# roomba_main_pcb_v1.net
KiCad netlist of a schematic drawn in EAGLE
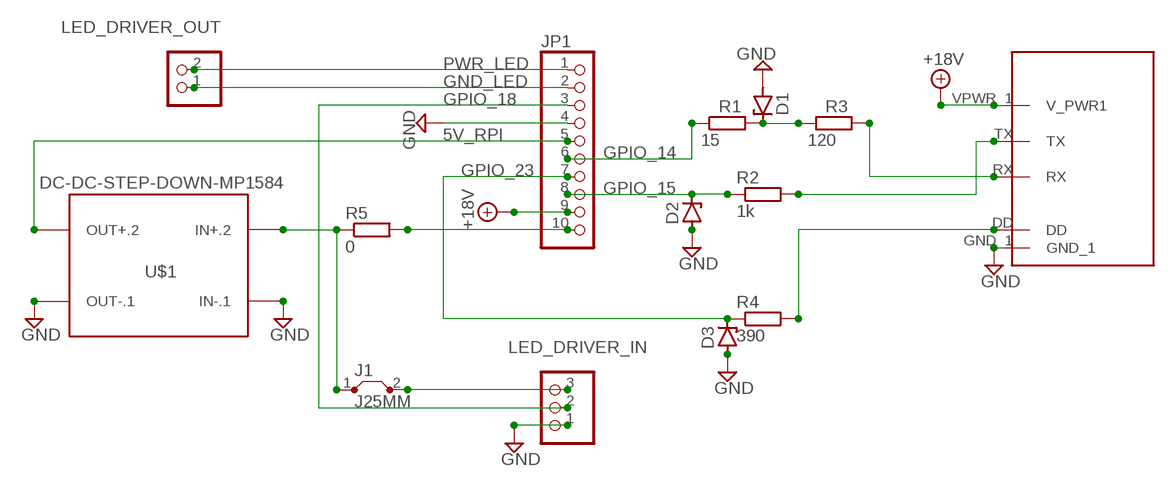
[diagram p0: schematic, sheet 1]

(export (version "E")
  (design (tool "Eeschema 10.0.6"))
  (components
    (comp (ref "D1")
      (value "ZENER-DIODESOD80C")
      (footprint "eagle-import:SOD80C")
      (libsource (lib "eagle-import") (part "ZENER-DIODESOD80C"))
    )
    (comp (ref "D2")
      (value "ZENER-DIODESOD80C")
      (footprint "eagle-import:SOD80C")
      (libsource (lib "eagle-import") (part "ZENER-DIODESOD80C"))
    )
    (comp (ref "D3")
      (value "ZENER-DIODESOD80C")
      (footprint "eagle-import:SOD80C")
      (libsource (lib "eagle-import") (part "ZENER-DIODESOD80C"))
    )
    (comp (ref "J1")
      (value "J25MM")
      (footprint "eagle-import:25")
      (libsource (lib "eagle-import") (part "J25MM"))
    )
    (comp (ref "JP1")
      (value "PINHD-1X10/90")
      (footprint "eagle-import:1X10_90")
      (libsource (lib "eagle-import") (part "PINHD-1X10/90"))
    )
    (comp (ref "LED_DRIVER_IN")
      (value "PINHD-1X3")
      (footprint "eagle-import:1X03")
      (libsource (lib "eagle-import") (part "PINHD-1X3"))
    )
    (comp (ref "LED_DRIVER_OUT")
      (value "PINHD-1X2")
      (footprint "eagle-import:1X02")
      (libsource (lib "eagle-import") (part "PINHD-1X2"))
    )
    (comp (ref "R1")
      (value "15")
      (footprint "eagle-import:M1206")
      (libsource (lib "eagle-import") (part "R-EU_M1206"))
    )
    (comp (ref "R2")
      (value "1k")
      (footprint "eagle-import:M1206")
      (libsource (lib "eagle-import") (part "R-EU_M1206"))
    )
    (comp (ref "R3")
      (value "120")
      (footprint "eagle-import:M1206")
      (libsource (lib "eagle-import") (part "R-EU_M1206"))
    )
    (comp (ref "R4")
      (value "390")
      (footprint "eagle-import:M1206")
      (libsource (lib "eagle-import") (part "R-EU_M1206"))
    )
    (comp (ref "R5")
      (value "0")
      (footprint "eagle-import:M1206")
      (libsource (lib "eagle-import") (part "R-EU_M1206"))
    )
    (comp (ref "ROOMBA_PORT")
      (value "7_PIN")
      (footprint "eagle-import:PIN-7")
      (libsource (lib "eagle-import") (part "7_PIN"))
    )
    (comp (ref "U$1")
      (value "DC-DC-STEP-DOWN-MP1584")
      (footprint "eagle-import:DC-DC-STEP-DOWN-MP1584")
      (libsource (lib "eagle-import") (part "DC-DC-STEP-DOWN-MP1584"))
    )
  )
  (nets
    (net (code "1") (name "+18V") (class "Default")
      (node (ref "JP1") (pin "9") (pinfunction "9_9") (pintype "passive"))
      (node (ref "ROOMBA_PORT") (pin "VPWR_1") (pinfunction "V_PWR1_VPWR_1") (pintype "bidirectional"))
    )
    (net (code "2") (name "/5V_RPI") (class "Default")
      (node (ref "JP1") (pin "5") (pinfunction "5_5") (pintype "passive"))
      (node (ref "U$1") (pin "OUT+.2") (pinfunction "OUT+.2_OUT+.2") (pintype "bidirectional"))
    )
    (net (code "3") (name "/GND_LED") (class "Default")
      (node (ref "JP1") (pin "2") (pinfunction "2_2") (pintype "passive"))
      (node (ref "LED_DRIVER_OUT") (pin "1") (pinfunction "1_1") (pintype "passive"))
    )
    (net (code "4") (name "/GPIO_14") (class "Default")
      (node (ref "JP1") (pin "6") (pinfunction "6_6") (pintype "passive"))
      (node (ref "R1") (pin "1") (pinfunction "1_1") (pintype "passive"))
    )
    (net (code "5") (name "/GPIO_15") (class "Default")
      (node (ref "D2") (pin "C") (pinfunction "C_C") (pintype "passive"))
      (node (ref "JP1") (pin "8") (pinfunction "8_8") (pintype "passive"))
      (node (ref "R2") (pin "1") (pinfunction "1_1") (pintype "passive"))
    )
    (net (code "6") (name "/GPIO_18") (class "Default")
      (node (ref "JP1") (pin "3") (pinfunction "3_3") (pintype "passive"))
      (node (ref "LED_DRIVER_IN") (pin "2") (pinfunction "2_2") (pintype "passive"))
    )
    (net (code "7") (name "/GPIO_23") (class "Default")
      (node (ref "D3") (pin "C") (pinfunction "C_C") (pintype "passive"))
      (node (ref "JP1") (pin "7") (pinfunction "7_7") (pintype "passive"))
      (node (ref "R4") (pin "1") (pinfunction "1_1") (pintype "passive"))
    )
    (net (code "8") (name "/PWR_LED") (class "Default")
      (node (ref "JP1") (pin "1") (pinfunction "1_1") (pintype "passive"))
      (node (ref "LED_DRIVER_OUT") (pin "2") (pinfunction "2_2") (pintype "passive"))
    )
    (net (code "9") (name "GND") (class "Default")
      (node (ref "D1") (pin "A") (pinfunction "A_A") (pintype "passive"))
      (node (ref "D2") (pin "A") (pinfunction "A_A") (pintype "passive"))
      (node (ref "D3") (pin "A") (pinfunction "A_A") (pintype "passive"))
      (node (ref "JP1") (pin "4") (pinfunction "4_4") (pintype "passive"))
      (node (ref "LED_DRIVER_IN") (pin "1") (pinfunction "1_1") (pintype "passive"))
      (node (ref "ROOMBA_PORT") (pin "GND_1") (pinfunction "GND_1_GND_1") (pintype "bidirectional"))
      (node (ref "U$1") (pin "IN-.1") (pinfunction "IN-.1_IN-.1") (pintype "bidirectional"))
      (node (ref "U$1") (pin "OUT-.1") (pinfunction "OUT-.1_OUT-.1") (pintype "bidirectional"))
    )
    (net (code "10") (name "Net-(D1-PadC)") (class "Default")
      (node (ref "D1") (pin "C") (pinfunction "C_C") (pintype "passive"))
      (node (ref "R1") (pin "2") (pinfunction "2_2") (pintype "passive"))
      (node (ref "R3") (pin "1") (pinfunction "1_1") (pintype "passive"))
    )
    (net (code "11") (name "Net-(J1-Pad1)") (class "Default")
      (node (ref "J1") (pin "1") (pinfunction "1_1") (pintype "passive"))
      (node (ref "R5") (pin "1") (pinfunction "1_1") (pintype "passive"))
      (node (ref "U$1") (pin "IN+.2") (pinfunction "IN+.2_IN+.2") (pintype "bidirectional"))
    )
    (net (code "12") (name "Net-(J1-Pad2)") (class "Default")
      (node (ref "J1") (pin "2") (pinfunction "2_2") (pintype "passive"))
      (node (ref "LED_DRIVER_IN") (pin "3") (pinfunction "3_3") (pintype "passive"))
    )
    (net (code "13") (name "Net-(JP1-Pad10)") (class "Default")
      (node (ref "JP1") (pin "10") (pinfunction "10_10") (pintype "passive"))
      (node (ref "R5") (pin "2") (pinfunction "2_2") (pintype "passive"))
    )
    (net (code "14") (name "Net-(R2-Pad2)") (class "Default")
      (node (ref "R2") (pin "2") (pinfunction "2_2") (pintype "passive"))
      (node (ref "ROOMBA_PORT") (pin "TX") (pinfunction "TX_TX") (pintype "bidirectional"))
    )
    (net (code "15") (name "Net-(R3-Pad2)") (class "Default")
      (node (ref "R3") (pin "2") (pinfunction "2_2") (pintype "passive"))
      (node (ref "ROOMBA_PORT") (pin "RX") (pinfunction "RX_RX") (pintype "bidirectional"))
    )
    (net (code "16") (name "Net-(R4-Pad2)") (class "Default")
      (node (ref "R4") (pin "2") (pinfunction "2_2") (pintype "passive"))
      (node (ref "ROOMBA_PORT") (pin "DD") (pinfunction "DD_DD") (pintype "bidirectional"))
    )
  )
)
